# SparkFun_Color_Sensor_OPT4048_Mini.net
KiCad netlist of a schematic drawn in EAGLE
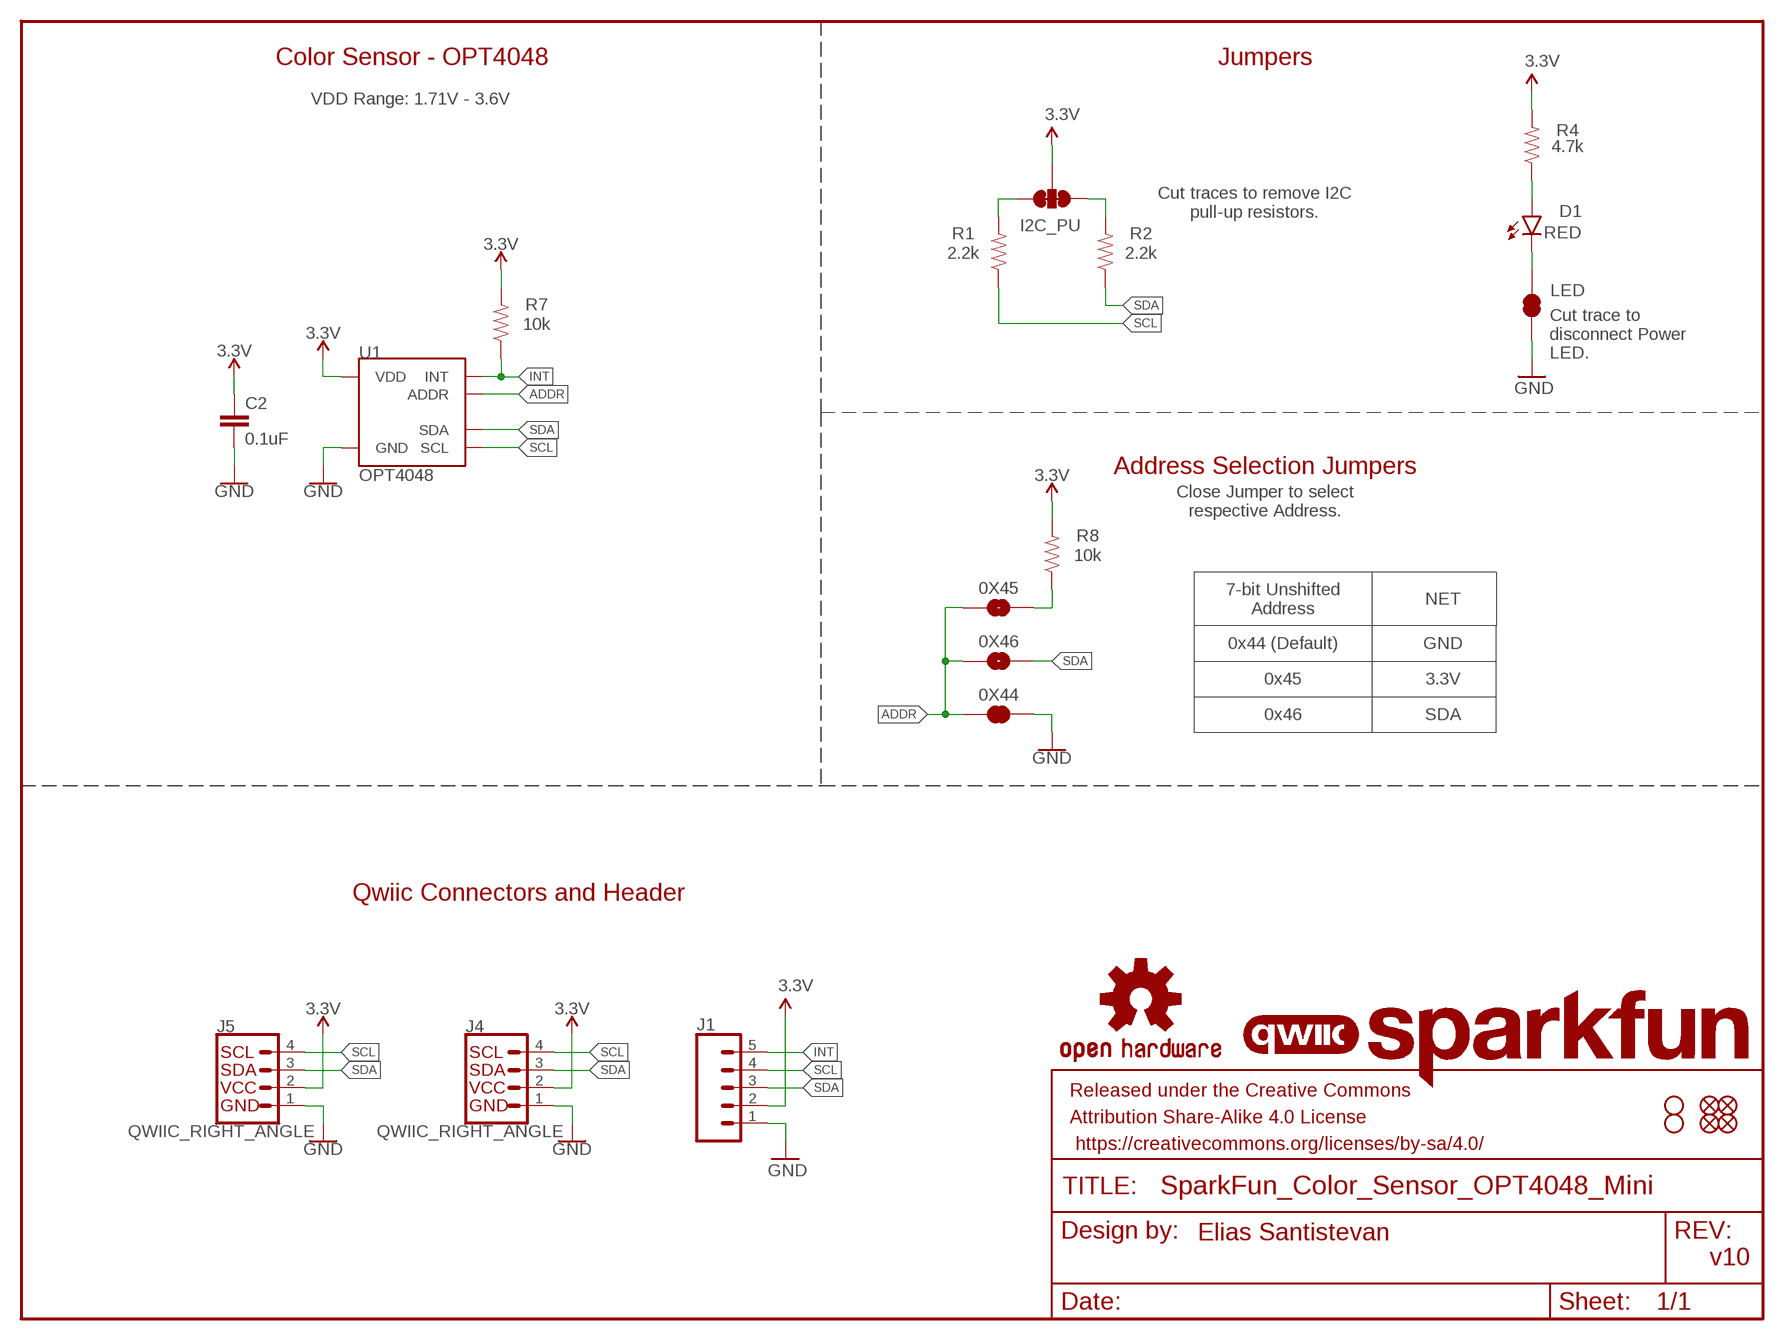
[diagram p0: schematic, sheet 1]

(export (version "E")
  (design (tool "Eeschema 10.0.6"))
  (components
    (comp (ref "0X44")
      (value "JUMPER-SMT_2_NC_TRACE_SILK")
      (footprint "eagle-import:SMT-JUMPER_2_NC_TRACE_SILK")
      (libsource (lib "eagle-import") (part "JUMPER-SMT_2_NC_TRACE_SILK"))
    )
    (comp (ref "0X45")
      (value "JUMPER-SMT_2_NO_SILK")
      (footprint "eagle-import:SMT-JUMPER_2_NO_SILK")
      (libsource (lib "eagle-import") (part "JUMPER-SMT_2_NO_SILK"))
    )
    (comp (ref "0X46")
      (value "JUMPER-SMT_2_NO_SILK")
      (footprint "eagle-import:SMT-JUMPER_2_NO_SILK")
      (libsource (lib "eagle-import") (part "JUMPER-SMT_2_NO_SILK"))
    )
    (comp (ref "C2")
      (value "0.1uF")
      (footprint "eagle-import:0402-TIGHT")
      (libsource (lib "eagle-import") (part "0.1UF-0402T-16V-10%"))
    )
    (comp (ref "D1")
      (value "RED")
      (footprint "eagle-import:LED-0603")
      (libsource (lib "eagle-import") (part "LED-RED_0603-KB"))
    )
    (comp (ref "FD5")
      (value "FIDUCIALUFIDUCIAL")
      (footprint "eagle-import:FIDUCIAL-MICRO")
      (libsource (lib "eagle-import") (part "FIDUCIALUFIDUCIAL"))
    )
    (comp (ref "FD6")
      (value "FIDUCIALUFIDUCIAL")
      (footprint "eagle-import:FIDUCIAL-MICRO")
      (libsource (lib "eagle-import") (part "FIDUCIALUFIDUCIAL"))
    )
    (comp (ref "FD7")
      (value "FIDUCIALUFIDUCIAL")
      (footprint "eagle-import:FIDUCIAL-MICRO")
      (libsource (lib "eagle-import") (part "FIDUCIALUFIDUCIAL"))
    )
    (comp (ref "FD8")
      (value "FIDUCIALUFIDUCIAL")
      (footprint "eagle-import:FIDUCIAL-MICRO")
      (libsource (lib "eagle-import") (part "FIDUCIALUFIDUCIAL"))
    )
    (comp (ref "FRAME2")
      (value "FRAME-LETTER")
      (footprint "eagle-import:CREATIVE_COMMONS")
      (libsource (lib "eagle-import") (part "FRAME-LETTER"))
    )
    (comp (ref "H7")
      (value "STAND-OFFTIGHT")
      (footprint "eagle-import:STAND-OFF-TIGHT")
      (libsource (lib "eagle-import") (part "STAND-OFFTIGHT"))
    )
    (comp (ref "H8")
      (value "STAND-OFFTIGHT")
      (footprint "eagle-import:STAND-OFF-TIGHT")
      (libsource (lib "eagle-import") (part "STAND-OFFTIGHT"))
    )
    (comp (ref "I2C_PU")
      (value "S_MODE")
      (footprint "eagle-import:SMT-JUMPER_3_2-NC_TRACE_SILK")
      (libsource (lib "eagle-import") (part "JUMPER-SMT_3_2-NC_TRACE_SILK"))
    )
    (comp (ref "J1")
      (value "CONN_05NO_SILK")
      (footprint "eagle-import:1X05_NO_SILK")
      (libsource (lib "eagle-import") (part "CONN_05NO_SILK"))
    )
    (comp (ref "J4")
      (value "QWIIC_RIGHT_ANGLE")
      (footprint "eagle-import:JST04_1MM_RA")
      (libsource (lib "eagle-import") (part "QWIIC_CONNECTORJS-1MM"))
    )
    (comp (ref "J5")
      (value "QWIIC_RIGHT_ANGLE")
      (footprint "eagle-import:JST04_1MM_RA")
      (libsource (lib "eagle-import") (part "QWIIC_CONNECTORJS-1MM"))
    )
    (comp (ref "LED")
      (value "JUMPER-SMT_2_NC_TRACE_SILK")
      (footprint "eagle-import:SMT-JUMPER_2_NC_TRACE_SILK")
      (libsource (lib "eagle-import") (part "JUMPER-SMT_2_NC_TRACE_SILK"))
    )
    (comp (ref "LOGO1")
      (value "SFE_LOGO_NAMEBLANK")
      (footprint "eagle-import:BLANK")
      (libsource (lib "eagle-import") (part "SFE_LOGO_NAMEBLANK"))
    )
    (comp (ref "LOGO2")
      (value "QWIIC_LOGO_3MM")
      (footprint "eagle-import:QWIIC_3MM")
      (libsource (lib "eagle-import") (part "QWIIC_LOGO_3MM"))
    )
    (comp (ref "LOGO3")
      (value "OSHW-LOGONO_SILK")
      (footprint "eagle-import:DUMMY")
      (libsource (lib "eagle-import") (part "OSHW-LOGONO_SILK"))
    )
    (comp (ref "R1")
      (value "2.2k")
      (footprint "eagle-import:0603")
      (libsource (lib "eagle-import") (part "2.2KOHM-0603-1/10W-1%"))
    )
    (comp (ref "R2")
      (value "2.2k")
      (footprint "eagle-import:0603")
      (libsource (lib "eagle-import") (part "2.2KOHM-0603-1/10W-1%"))
    )
    (comp (ref "R4")
      (value "4.7k")
      (footprint "eagle-import:0603")
      (libsource (lib "eagle-import") (part "4.7KOHM-0603-1/10W-1%"))
    )
    (comp (ref "R7")
      (value "10k")
      (footprint "eagle-import:0603")
      (libsource (lib "eagle-import") (part "10KOHM-0603-1/10W-1%"))
    )
    (comp (ref "R8")
      (value "10k")
      (footprint "eagle-import:0603")
      (libsource (lib "eagle-import") (part "10KOHM-0603-1/10W-1%"))
    )
    (comp (ref "U1")
      (value "OPT4048")
      (footprint "eagle-import:FCSOT")
      (libsource (lib "eagle-import") (part "OPT4048"))
    )
  )
  (nets
    (net (code "1") (name "3.3V") (class "Default")
      (node (ref "C2") (pin "1") (pinfunction "1_1") (pintype "passive"))
      (node (ref "I2C_PU") (pin "2") (pinfunction "2_2") (pintype "passive"))
      (node (ref "J1") (pin "2") (pinfunction "2_2") (pintype "passive"))
      (node (ref "J4") (pin "2") (pinfunction "2_2") (pintype "power_in"))
      (node (ref "J5") (pin "2") (pinfunction "2_2") (pintype "power_in"))
      (node (ref "R4") (pin "2") (pinfunction "2_2") (pintype "passive"))
      (node (ref "R7") (pin "2") (pinfunction "2_2") (pintype "passive"))
      (node (ref "R8") (pin "2") (pinfunction "2_2") (pintype "passive"))
      (node (ref "U1") (pin "P1") (pinfunction "VDD_P1") (pintype "bidirectional"))
    )
    (net (code "2") (name "ADDR") (class "Default")
      (node (ref "0X44") (pin "1") (pinfunction "1_1") (pintype "passive"))
      (node (ref "0X45") (pin "1") (pinfunction "1_1") (pintype "passive"))
      (node (ref "0X46") (pin "1") (pinfunction "1_1") (pintype "passive"))
      (node (ref "U1") (pin "P2") (pinfunction "ADDR_P2") (pintype "bidirectional"))
    )
    (net (code "3") (name "GND") (class "Default")
      (node (ref "0X44") (pin "2") (pinfunction "2_2") (pintype "passive"))
      (node (ref "C2") (pin "2") (pinfunction "2_2") (pintype "passive"))
      (node (ref "J1") (pin "1") (pinfunction "1_1") (pintype "passive"))
      (node (ref "J4") (pin "1") (pinfunction "1_1") (pintype "power_in"))
      (node (ref "J5") (pin "1") (pinfunction "1_1") (pintype "power_in"))
      (node (ref "LED") (pin "1") (pinfunction "1_1") (pintype "passive"))
      (node (ref "U1") (pin "P4") (pinfunction "GND_P4") (pintype "bidirectional"))
    )
    (net (code "4") (name "INT") (class "Default")
      (node (ref "J1") (pin "5") (pinfunction "5_5") (pintype "passive"))
      (node (ref "R7") (pin "1") (pinfunction "1_1") (pintype "passive"))
      (node (ref "U1") (pin "P7") (pinfunction "INT_P7") (pintype "bidirectional"))
    )
    (net (code "5") (name "Net-(0X45-Pad2)") (class "Default")
      (node (ref "0X45") (pin "2") (pinfunction "2_2") (pintype "passive"))
      (node (ref "R8") (pin "1") (pinfunction "1_1") (pintype "passive"))
    )
    (net (code "6") (name "Net-(D1-PadA)") (class "Default")
      (node (ref "D1") (pin "A") (pinfunction "A_A") (pintype "passive"))
      (node (ref "R4") (pin "1") (pinfunction "1_1") (pintype "passive"))
    )
    (net (code "7") (name "Net-(D1-PadC)") (class "Default")
      (node (ref "D1") (pin "C") (pinfunction "C_C") (pintype "passive"))
      (node (ref "LED") (pin "2") (pinfunction "2_2") (pintype "passive"))
    )
    (net (code "8") (name "Net-(I2C_PU-Pad1)") (class "Default")
      (node (ref "I2C_PU") (pin "1") (pinfunction "1_1") (pintype "passive"))
      (node (ref "R1") (pin "2") (pinfunction "2_2") (pintype "passive"))
    )
    (net (code "9") (name "Net-(I2C_PU-Pad3)") (class "Default")
      (node (ref "I2C_PU") (pin "3") (pinfunction "3_3") (pintype "passive"))
      (node (ref "R2") (pin "2") (pinfunction "2_2") (pintype "passive"))
    )
    (net (code "10") (name "SCL") (class "Default")
      (node (ref "J1") (pin "4") (pinfunction "4_4") (pintype "passive"))
      (node (ref "J4") (pin "4") (pinfunction "4_4") (pintype "passive"))
      (node (ref "J5") (pin "4") (pinfunction "4_4") (pintype "passive"))
      (node (ref "R1") (pin "1") (pinfunction "1_1") (pintype "passive"))
      (node (ref "U1") (pin "P5") (pinfunction "SCL_P5") (pintype "bidirectional"))
    )
    (net (code "11") (name "SDA") (class "Default")
      (node (ref "0X46") (pin "2") (pinfunction "2_2") (pintype "passive"))
      (node (ref "J1") (pin "3") (pinfunction "3_3") (pintype "passive"))
      (node (ref "J4") (pin "3") (pinfunction "3_3") (pintype "passive"))
      (node (ref "J5") (pin "3") (pinfunction "3_3") (pintype "passive"))
      (node (ref "R2") (pin "1") (pinfunction "1_1") (pintype "passive"))
      (node (ref "U1") (pin "P8") (pinfunction "SDA_P8") (pintype "bidirectional"))
    )
  )
)
